# power.net
KiCad netlist of a schematic drawn in Altium Designer
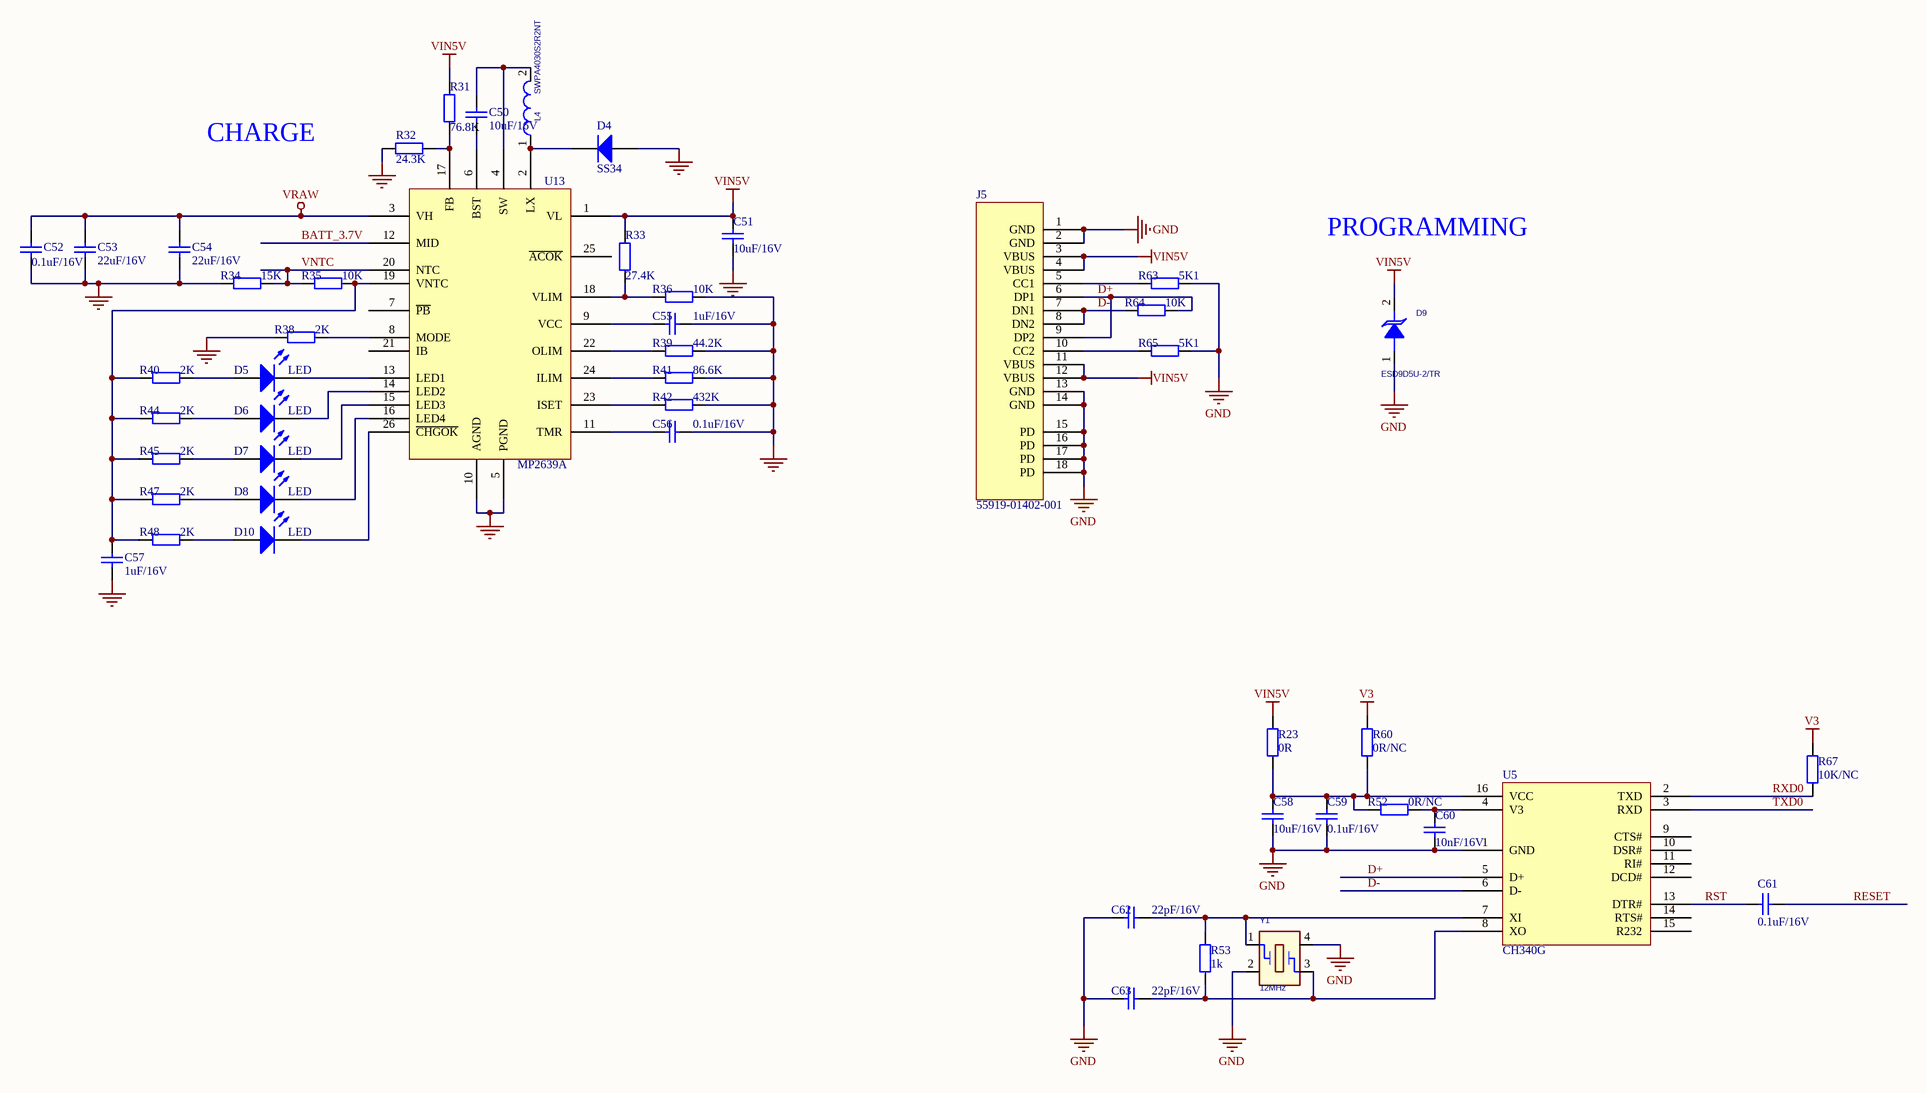
[diagram p0: power.SchDoc]

(export (version "E")
  (design (tool "Eeschema 10.0.6"))
  (components
    (comp (ref "C50")
      (value "10uF/16V")
      (footprint "CAPC1608N")
      (description "Capacitor")
      (libsource (lib "altium-import") (part "root_1_Cap_2_"))
    )
    (comp (ref "C51")
      (value "10uF/16V")
      (footprint "CAPC1608N")
      (description "Capacitor")
      (libsource (lib "altium-import") (part "root_1_Cap_2_"))
    )
    (comp (ref "C52")
      (value "0.1uF/16V")
      (footprint "CAPC1608N")
      (description "Capacitor")
      (libsource (lib "altium-import") (part "root_1_Cap_2_"))
    )
    (comp (ref "C53")
      (value "22uF/16V")
      (footprint "CAPC2012N")
      (description "Capacitor")
      (libsource (lib "altium-import") (part "root_1_Cap_2_"))
    )
    (comp (ref "C54")
      (value "22uF/16V")
      (footprint "CAPC2012N")
      (description "Capacitor")
      (libsource (lib "altium-import") (part "root_1_Cap_2_"))
    )
    (comp (ref "C55")
      (value "1uF/16V")
      (footprint "CAPC1608N")
      (description "Capacitor")
      (libsource (lib "altium-import") (part "root_2_Cap_2_"))
    )
    (comp (ref "C56")
      (value "0.1uF/16V")
      (footprint "CAPC1608N")
      (description "Capacitor")
      (libsource (lib "altium-import") (part "root_2_Cap_2_"))
    )
    (comp (ref "C57")
      (value "1uF/16V")
      (footprint "CAPC1608N")
      (description "Capacitor")
      (libsource (lib "altium-import") (part "root_1_Cap_2_"))
    )
    (comp (ref "C58")
      (value "10uF/16V")
      (footprint "CAPC1608N")
      (description "Capacitor")
      (libsource (lib "altium-import") (part "root_3_Cap_2_"))
    )
    (comp (ref "C59")
      (value "0.1uF/16V")
      (footprint "CAPC1608N")
      (description "Capacitor")
      (libsource (lib "altium-import") (part "root_3_Cap_2_"))
    )
    (comp (ref "C60")
      (value "10nF/16V")
      (footprint "CAPC1608N")
      (description "Capacitor")
      (libsource (lib "altium-import") (part "root_3_Cap_2_"))
    )
    (comp (ref "C61")
      (value "0.1uF/16V")
      (footprint "CAPC1608N")
      (description "Capacitor")
      (libsource (lib "altium-import") (part "root_0_Cap_2_"))
    )
    (comp (ref "C62")
      (value "22pF/16V")
      (footprint "CAPC1608N")
      (description "Capacitor")
      (libsource (lib "altium-import") (part "root_2_Cap_2_"))
    )
    (comp (ref "C63")
      (value "22pF/16V")
      (footprint "CAPC1608N")
      (description "Capacitor")
      (libsource (lib "altium-import") (part "root_2_Cap_2_"))
    )
    (comp (ref "D4")
      (value "SS34")
      (footprint "SMB")
      (description "Default Diode")
      (fields (field (name "PUBLISHER") "Altium Limited"))
      (libsource (lib "Component") (part "DIODE"))
    )
    (comp (ref "D5")
      (value "LED")
      (footprint "0603LED G")
      (description "Typical INFRARED GaAs LED")
      (fields (field (name "PUBLISHER") "Altium Limited"))
      (libsource (lib "Miscellaneous Devices") (part "LED0"))
    )
    (comp (ref "D6")
      (value "LED")
      (footprint "0603LED G")
      (description "Typical INFRARED GaAs LED")
      (fields (field (name "PUBLISHER") "Altium Limited"))
      (libsource (lib "Miscellaneous Devices") (part "LED0"))
    )
    (comp (ref "D7")
      (value "LED")
      (footprint "0603LED G")
      (description "Typical INFRARED GaAs LED")
      (fields (field (name "PUBLISHER") "Altium Limited"))
      (libsource (lib "Miscellaneous Devices") (part "LED0"))
    )
    (comp (ref "D8")
      (value "LED")
      (footprint "0603LED G")
      (description "Typical INFRARED GaAs LED")
      (fields (field (name "PUBLISHER") "Altium Limited"))
      (libsource (lib "Miscellaneous Devices") (part "LED0"))
    )
    (comp (ref "D9")
      (value "ESD9D5U-2/TR")
      (footprint "sod-923")
      (description "DIODE TVS ESD PROT ULT LOW CAP 5-5.4V SOD-923")
      (libsource (lib "*") (part "DIODE_TVS"))
    )
    (comp (ref "D10")
      (value "LED")
      (footprint "0603LED G")
      (description "Typical INFRARED GaAs LED")
      (fields (field (name "PUBLISHER") "Altium Limited"))
      (libsource (lib "Miscellaneous Devices") (part "LED0"))
    )
    (comp (ref "J5")
      (value "55919-01402-001")
      (footprint "55919-01402-001")
      (libsource (lib "COMMODEVICES") (part "55919-01402-001"))
    )
    (comp (ref "L4")
      (value "SWPA4030S2R2NT")
      (footprint "L4X4")
      (description "Inductor 2.2uH smt 2.6A, 58 milliohm")
      (fields (field (name "MFR") "TDK") (field (name "TIINTPARTNUMBER") "1L0025"))
      (libsource (lib "*") (part "IND_2.2uH_2.6A_10%_SMD"))
    )
    (comp (ref "R23")
      (value "0R")
      (footprint "RESC1608N")
      (description "Resistor")
      (libsource (lib "") (part "Res2_2"))
    )
    (comp (ref "R31")
      (value "76.8K")
      (footprint "RESC1608N")
      (description "Resistor")
      (libsource (lib "") (part "Res2_2"))
    )
    (comp (ref "R32")
      (value "24.3K")
      (footprint "RESC1608N")
      (description "Resistor")
      (libsource (lib "") (part "Res2_1"))
    )
    (comp (ref "R33")
      (value "27.4K")
      (footprint "RESC1608N")
      (description "Resistor")
      (libsource (lib "") (part "Res2_2"))
    )
    (comp (ref "R34")
      (value "15K")
      (footprint "RESC1608N")
      (description "Resistor")
      (libsource (lib "*") (part "Res2"))
    )
    (comp (ref "R35")
      (value "10K")
      (footprint "RESC1608N")
      (description "Resistor")
      (libsource (lib "*") (part "Res2"))
    )
    (comp (ref "R36")
      (value "10K")
      (footprint "RESC1608N")
      (description "Resistor")
      (libsource (lib "") (part "Res2_1"))
    )
    (comp (ref "R38")
      (value "2K")
      (footprint "RESC1608N")
      (description "Resistor")
      (libsource (lib "*") (part "Res2"))
    )
    (comp (ref "R39")
      (value "44.2K")
      (footprint "RESC1608N")
      (description "Resistor")
      (libsource (lib "") (part "Res2_1"))
    )
    (comp (ref "R40")
      (value "2K")
      (footprint "RESC1608N")
      (description "Resistor")
      (libsource (lib "*") (part "Res2"))
    )
    (comp (ref "R41")
      (value "86.6K")
      (footprint "RESC1608N")
      (description "Resistor")
      (libsource (lib "") (part "Res2_1"))
    )
    (comp (ref "R42")
      (value "432K")
      (footprint "RESC1608N")
      (description "Resistor")
      (libsource (lib "") (part "Res2_1"))
    )
    (comp (ref "R44")
      (value "2K")
      (footprint "RESC1608N")
      (description "Resistor")
      (libsource (lib "*") (part "Res2"))
    )
    (comp (ref "R45")
      (value "2K")
      (footprint "RESC1608N")
      (description "Resistor")
      (libsource (lib "*") (part "Res2"))
    )
    (comp (ref "R47")
      (value "2K")
      (footprint "RESC1608N")
      (description "Resistor")
      (libsource (lib "*") (part "Res2"))
    )
    (comp (ref "R48")
      (value "2K")
      (footprint "RESC1608N")
      (description "Resistor")
      (libsource (lib "*") (part "Res2"))
    )
    (comp (ref "R52")
      (value "0R/NC")
      (footprint "RESC1608N")
      (description "Resistor")
      (libsource (lib "*") (part "Res2"))
    )
    (comp (ref "R53")
      (value "1k")
      (footprint "RESC1608N")
      (description "Resistor")
      (fields (field (name "PUBLISHER") "Altium Limited"))
      (libsource (lib "*") (part "Res2"))
    )
    (comp (ref "R60")
      (value "0R/NC")
      (footprint "RESC1608N")
      (description "Resistor")
      (libsource (lib "") (part "Res2_2"))
    )
    (comp (ref "R63")
      (value "5K1")
      (footprint "RESC1608N")
      (description "Resistor")
      (libsource (lib "*") (part "Res2"))
    )
    (comp (ref "R64")
      (value "10K")
      (footprint "RESC1608N")
      (description "Resistor")
      (libsource (lib "") (part "Res2_1"))
    )
    (comp (ref "R65")
      (value "5K1")
      (footprint "RESC1608N")
      (description "Resistor")
      (libsource (lib "*") (part "Res2"))
    )
    (comp (ref "R67")
      (value "10K/NC")
      (footprint "RESC1608N")
      (description "Resistor")
      (libsource (lib "") (part "Res2_2"))
    )
    (comp (ref "U5") (value "CH340G") (footprint "sop16") (libsource (lib "COMMODEVICES") (part "CH340G")))
    (comp (ref "U13") (value "MP2639A") (footprint "MP2639A") (libsource (lib "plobot") (part "MP2639A")))
    (comp (ref "Y1") (value "12MHz") (footprint "XTAL-3225") (libsource (lib "*") (part "XTAL_13Y_A")))
  )
  (nets
    (net (code "1") (name "/BATT_3.7V") (class "Default")
      (node (ref "U13") (pin "12") (pinfunction "MID_12") (pintype "power_in"))
    )
    (net (code "2") (name "/D+") (class "Default")
      (node (ref "J5") (pin "6") (pinfunction "DP1_6") (pintype "passive"))
      (node (ref "J5") (pin "9") (pinfunction "DP2_9") (pintype "passive"))
      (node (ref "R64") (pin "2") (pinfunction "2_2") (pintype "passive"))
      (node (ref "U5") (pin "5") (pinfunction "D+_5") (pintype "passive"))
    )
    (net (code "3") (name "/D-") (class "Default")
      (node (ref "J5") (pin "7") (pinfunction "DN1_7") (pintype "passive"))
      (node (ref "J5") (pin "8") (pinfunction "DN2_8") (pintype "passive"))
      (node (ref "R64") (pin "1") (pinfunction "1_1") (pintype "passive"))
      (node (ref "U5") (pin "6") (pinfunction "D-_6") (pintype "passive"))
    )
    (net (code "4") (name "/RESET") (class "Default")
      (node (ref "C61") (pin "2") (pinfunction "2_2") (pintype "passive"))
    )
    (net (code "5") (name "/RST") (class "Default")
      (node (ref "C61") (pin "1") (pinfunction "1_1") (pintype "passive"))
      (node (ref "U5") (pin "13") (pinfunction "DTR#_13") (pintype "passive"))
    )
    (net (code "6") (name "/RXD0") (class "Default")
      (node (ref "R67") (pin "2") (pinfunction "2_2") (pintype "passive"))
      (node (ref "U5") (pin "2") (pinfunction "TXD_2") (pintype "passive"))
    )
    (net (code "7") (name "/TXD0") (class "Default")
      (node (ref "U5") (pin "3") (pinfunction "RXD_3") (pintype "passive"))
    )
    (net (code "8") (name "/VNTC") (class "Default")
      (node (ref "R34") (pin "1") (pinfunction "1_1") (pintype "passive"))
      (node (ref "R35") (pin "2") (pinfunction "2_2") (pintype "passive"))
      (node (ref "U13") (pin "20") (pinfunction "NTC_20") (pintype "power_in"))
    )
    (net (code "9") (name "GND") (class "Default")
      (node (ref "C51") (pin "1") (pinfunction "1_1") (pintype "passive"))
      (node (ref "C52") (pin "1") (pinfunction "1_1") (pintype "passive"))
      (node (ref "C53") (pin "1") (pinfunction "1_1") (pintype "passive"))
      (node (ref "C54") (pin "1") (pinfunction "1_1") (pintype "passive"))
      (node (ref "C55") (pin "1") (pinfunction "1_1") (pintype "passive"))
      (node (ref "C56") (pin "1") (pinfunction "1_1") (pintype "passive"))
      (node (ref "C57") (pin "1") (pinfunction "1_1") (pintype "passive"))
      (node (ref "C58") (pin "2") (pinfunction "2_2") (pintype "passive"))
      (node (ref "C59") (pin "2") (pinfunction "2_2") (pintype "passive"))
      (node (ref "C60") (pin "2") (pinfunction "2_2") (pintype "passive"))
      (node (ref "C62") (pin "2") (pinfunction "2_2") (pintype "passive"))
      (node (ref "C63") (pin "2") (pinfunction "2_2") (pintype "passive"))
      (node (ref "D4") (pin "1") (pinfunction "A_1") (pintype "passive"))
      (node (ref "D9") (pin "1") (pinfunction "1_1") (pintype "passive"))
      (node (ref "J5") (pin "1") (pinfunction "GND_1") (pintype "passive"))
      (node (ref "J5") (pin "13") (pinfunction "GND_13") (pintype "passive"))
      (node (ref "J5") (pin "14") (pinfunction "GND_14") (pintype "passive"))
      (node (ref "J5") (pin "15") (pinfunction "PD_15") (pintype "passive"))
      (node (ref "J5") (pin "16") (pinfunction "PD_16") (pintype "passive"))
      (node (ref "J5") (pin "17") (pinfunction "PD_17") (pintype "passive"))
      (node (ref "J5") (pin "18") (pinfunction "PD_18") (pintype "passive"))
      (node (ref "J5") (pin "2") (pinfunction "GND_2") (pintype "passive"))
      (node (ref "R32") (pin "1") (pinfunction "1_1") (pintype "passive"))
      (node (ref "R34") (pin "2") (pinfunction "2_2") (pintype "passive"))
      (node (ref "R36") (pin "2") (pinfunction "2_2") (pintype "passive"))
      (node (ref "R38") (pin "2") (pinfunction "2_2") (pintype "passive"))
      (node (ref "R39") (pin "2") (pinfunction "2_2") (pintype "passive"))
      (node (ref "R41") (pin "2") (pinfunction "2_2") (pintype "passive"))
      (node (ref "R42") (pin "2") (pinfunction "2_2") (pintype "passive"))
      (node (ref "R63") (pin "1") (pinfunction "1_1") (pintype "passive"))
      (node (ref "R65") (pin "1") (pinfunction "1_1") (pintype "passive"))
      (node (ref "U13") (pin "10") (pinfunction "AGND_10") (pintype "power_in"))
      (node (ref "U13") (pin "5") (pinfunction "PGND_5") (pintype "power_in"))
      (node (ref "U5") (pin "1") (pinfunction "GND_1") (pintype "passive"))
      (node (ref "Y1") (pin "2") (pinfunction "2_2") (pintype "passive"))
      (node (ref "Y1") (pin "4") (pinfunction "4_4") (pintype "passive"))
    )
    (net (code "10") (name "Net-(D4-K)") (class "Default")
      (node (ref "D4") (pin "2") (pinfunction "K_2") (pintype "passive"))
      (node (ref "L4") (pin "1") (pinfunction "1_1") (pintype "passive"))
      (node (ref "U13") (pin "2") (pinfunction "LX_2") (pintype "power_in"))
    )
    (net (code "11") (name "Net-(D5-A)") (class "Default")
      (node (ref "D5") (pin "1") (pinfunction "A_1") (pintype "passive"))
      (node (ref "R40") (pin "1") (pinfunction "1_1") (pintype "passive"))
    )
    (net (code "12") (name "Net-(D5-K)") (class "Default")
      (node (ref "D5") (pin "2") (pinfunction "K_2") (pintype "passive"))
      (node (ref "U13") (pin "13") (pinfunction "LED1_13") (pintype "power_in"))
    )
    (net (code "13") (name "Net-(D6-A)") (class "Default")
      (node (ref "D6") (pin "1") (pinfunction "A_1") (pintype "passive"))
      (node (ref "R44") (pin "1") (pinfunction "1_1") (pintype "passive"))
    )
    (net (code "14") (name "Net-(D6-K)") (class "Default")
      (node (ref "D6") (pin "2") (pinfunction "K_2") (pintype "passive"))
      (node (ref "U13") (pin "14") (pinfunction "LED2_14") (pintype "power_in"))
    )
    (net (code "15") (name "Net-(D7-A)") (class "Default")
      (node (ref "D7") (pin "1") (pinfunction "A_1") (pintype "passive"))
      (node (ref "R45") (pin "1") (pinfunction "1_1") (pintype "passive"))
    )
    (net (code "16") (name "Net-(D7-K)") (class "Default")
      (node (ref "D7") (pin "2") (pinfunction "K_2") (pintype "passive"))
      (node (ref "U13") (pin "15") (pinfunction "LED3_15") (pintype "power_in"))
    )
    (net (code "17") (name "Net-(D8-A)") (class "Default")
      (node (ref "D8") (pin "1") (pinfunction "A_1") (pintype "passive"))
      (node (ref "R47") (pin "1") (pinfunction "1_1") (pintype "passive"))
    )
    (net (code "18") (name "Net-(D8-K)") (class "Default")
      (node (ref "D8") (pin "2") (pinfunction "K_2") (pintype "passive"))
      (node (ref "U13") (pin "16") (pinfunction "LED4_16") (pintype "power_in"))
    )
    (net (code "19") (name "Net-(D10-A)") (class "Default")
      (node (ref "D10") (pin "1") (pinfunction "A_1") (pintype "passive"))
      (node (ref "R48") (pin "1") (pinfunction "1_1") (pintype "passive"))
    )
    (net (code "20") (name "Net-(D10-K)") (class "Default")
      (node (ref "D10") (pin "2") (pinfunction "K_2") (pintype "passive"))
      (node (ref "U13") (pin "26") (pinfunction "~{CHGOK}_26") (pintype "power_in"))
    )
    (net (code "21") (name "Net-(J5-CC1)") (class "Default")
      (node (ref "J5") (pin "5") (pinfunction "CC1_5") (pintype "passive"))
      (node (ref "R63") (pin "2") (pinfunction "2_2") (pintype "passive"))
    )
    (net (code "22") (name "Net-(J5-CC2)") (class "Default")
      (node (ref "J5") (pin "10") (pinfunction "CC2_10") (pintype "passive"))
      (node (ref "R65") (pin "2") (pinfunction "2_2") (pintype "passive"))
    )
    (net (code "23") (name "Net-(U5-V3)") (class "Default")
      (node (ref "C60") (pin "1") (pinfunction "1_1") (pintype "passive"))
      (node (ref "R52") (pin "1") (pinfunction "1_1") (pintype "passive"))
      (node (ref "U5") (pin "4") (pinfunction "V3_4") (pintype "passive"))
    )
    (net (code "24") (name "Net-(U5-VCC)") (class "Default")
      (node (ref "C58") (pin "1") (pinfunction "1_1") (pintype "passive"))
      (node (ref "C59") (pin "1") (pinfunction "1_1") (pintype "passive"))
      (node (ref "R23") (pin "2") (pinfunction "2_2") (pintype "passive"))
      (node (ref "R52") (pin "2") (pinfunction "2_2") (pintype "passive"))
      (node (ref "R60") (pin "2") (pinfunction "2_2") (pintype "passive"))
      (node (ref "U5") (pin "16") (pinfunction "VCC_16") (pintype "passive"))
    )
    (net (code "25") (name "Net-(U5-XI)") (class "Default")
      (node (ref "C62") (pin "1") (pinfunction "1_1") (pintype "passive"))
      (node (ref "R53") (pin "1") (pinfunction "1_1") (pintype "passive"))
      (node (ref "U5") (pin "7") (pinfunction "XI_7") (pintype "passive"))
      (node (ref "Y1") (pin "1") (pinfunction "1_1") (pintype "passive"))
    )
    (net (code "26") (name "Net-(U5-XO)") (class "Default")
      (node (ref "C63") (pin "1") (pinfunction "1_1") (pintype "passive"))
      (node (ref "R53") (pin "2") (pinfunction "2_2") (pintype "passive"))
      (node (ref "U5") (pin "8") (pinfunction "XO_8") (pintype "passive"))
      (node (ref "Y1") (pin "3") (pinfunction "3_3") (pintype "passive"))
    )
    (net (code "27") (name "Net-(U13-BST)") (class "Default")
      (node (ref "C50") (pin "1") (pinfunction "1_1") (pintype "passive"))
      (node (ref "U13") (pin "6") (pinfunction "BST_6") (pintype "power_in"))
    )
    (net (code "28") (name "Net-(U13-FB)") (class "Default")
      (node (ref "R31") (pin "2") (pinfunction "2_2") (pintype "passive"))
      (node (ref "R32") (pin "2") (pinfunction "2_2") (pintype "passive"))
      (node (ref "U13") (pin "17") (pinfunction "FB_17") (pintype "power_in"))
    )
    (net (code "29") (name "Net-(U13-ILIM)") (class "Default")
      (node (ref "R41") (pin "1") (pinfunction "1_1") (pintype "passive"))
      (node (ref "U13") (pin "24") (pinfunction "ILIM_24") (pintype "power_in"))
    )
    (net (code "30") (name "Net-(U13-ISET)") (class "Default")
      (node (ref "R42") (pin "1") (pinfunction "1_1") (pintype "passive"))
      (node (ref "U13") (pin "23") (pinfunction "ISET_23") (pintype "power_in"))
    )
    (net (code "31") (name "Net-(U13-MODE)") (class "Default")
      (node (ref "R38") (pin "1") (pinfunction "1_1") (pintype "passive"))
      (node (ref "U13") (pin "8") (pinfunction "MODE_8") (pintype "power_in"))
    )
    (net (code "32") (name "Net-(U13-OLIM)") (class "Default")
      (node (ref "R39") (pin "1") (pinfunction "1_1") (pintype "passive"))
      (node (ref "U13") (pin "22") (pinfunction "OLIM_22") (pintype "power_in"))
    )
    (net (code "33") (name "Net-(U13-SW)") (class "Default")
      (node (ref "C50") (pin "2") (pinfunction "2_2") (pintype "passive"))
      (node (ref "L4") (pin "2") (pinfunction "2_2") (pintype "passive"))
      (node (ref "U13") (pin "4") (pinfunction "SW_4") (pintype "power_in"))
    )
    (net (code "34") (name "Net-(U13-TMR)") (class "Default")
      (node (ref "C56") (pin "2") (pinfunction "2_2") (pintype "passive"))
      (node (ref "U13") (pin "11") (pinfunction "TMR_11") (pintype "power_in"))
    )
    (net (code "35") (name "Net-(U13-VCC)") (class "Default")
      (node (ref "C55") (pin "2") (pinfunction "2_2") (pintype "passive"))
      (node (ref "U13") (pin "9") (pinfunction "VCC_9") (pintype "power_in"))
    )
    (net (code "36") (name "Net-(U13-VLIM)") (class "Default")
      (node (ref "R33") (pin "2") (pinfunction "2_2") (pintype "passive"))
      (node (ref "R36") (pin "1") (pinfunction "1_1") (pintype "passive"))
      (node (ref "U13") (pin "18") (pinfunction "VLIM_18") (pintype "power_in"))
    )
    (net (code "37") (name "Net-(U13-VNTC)") (class "Default")
      (node (ref "C57") (pin "2") (pinfunction "2_2") (pintype "passive"))
      (node (ref "R35") (pin "1") (pinfunction "1_1") (pintype "passive"))
      (node (ref "R40") (pin "2") (pinfunction "2_2") (pintype "passive"))
      (node (ref "R44") (pin "2") (pinfunction "2_2") (pintype "passive"))
      (node (ref "R45") (pin "2") (pinfunction "2_2") (pintype "passive"))
      (node (ref "R47") (pin "2") (pinfunction "2_2") (pintype "passive"))
      (node (ref "R48") (pin "2") (pinfunction "2_2") (pintype "passive"))
      (node (ref "U13") (pin "19") (pinfunction "VNTC_19") (pintype "power_in"))
    )
    (net (code "38") (name "V3") (class "Default")
      (node (ref "R60") (pin "1") (pinfunction "1_1") (pintype "passive"))
      (node (ref "R67") (pin "1") (pinfunction "1_1") (pintype "passive"))
    )
    (net (code "39") (name "VIN5V") (class "Default")
      (node (ref "C51") (pin "2") (pinfunction "2_2") (pintype "passive"))
      (node (ref "D9") (pin "2") (pinfunction "2_2") (pintype "passive"))
      (node (ref "J5") (pin "11") (pinfunction "VBUS_11") (pintype "passive"))
      (node (ref "J5") (pin "12") (pinfunction "VBUS_12") (pintype "passive"))
      (node (ref "J5") (pin "3") (pinfunction "VBUS_3") (pintype "passive"))
      (node (ref "J5") (pin "4") (pinfunction "VBUS_4") (pintype "passive"))
      (node (ref "R23") (pin "1") (pinfunction "1_1") (pintype "passive"))
      (node (ref "R31") (pin "1") (pinfunction "1_1") (pintype "passive"))
      (node (ref "R33") (pin "1") (pinfunction "1_1") (pintype "passive"))
      (node (ref "U13") (pin "1") (pinfunction "VL_1") (pintype "power_in"))
    )
    (net (code "40") (name "VRAW") (class "Default")
      (node (ref "C52") (pin "2") (pinfunction "2_2") (pintype "passive"))
      (node (ref "C53") (pin "2") (pinfunction "2_2") (pintype "passive"))
      (node (ref "C54") (pin "2") (pinfunction "2_2") (pintype "passive"))
      (node (ref "U13") (pin "3") (pinfunction "VH_3") (pintype "power_in"))
    )
    (net (code "41") (name "unconnected-(U5-CTS#-Pad9)") (class "Default")
      (node (ref "U5") (pin "9") (pinfunction "CTS#_9") (pintype "passive"))
    )
    (net (code "42") (name "unconnected-(U5-DCD#-Pad12)") (class "Default")
      (node (ref "U5") (pin "12") (pinfunction "DCD#_12") (pintype "passive"))
    )
    (net (code "43") (name "unconnected-(U5-DSR#-Pad10)") (class "Default")
      (node (ref "U5") (pin "10") (pinfunction "DSR#_10") (pintype "passive"))
    )
    (net (code "44") (name "unconnected-(U5-R232-Pad15)") (class "Default")
      (node (ref "U5") (pin "15") (pinfunction "R232_15") (pintype "passive"))
    )
    (net (code "45") (name "unconnected-(U5-RI#-Pad11)") (class "Default")
      (node (ref "U5") (pin "11") (pinfunction "RI#_11") (pintype "passive"))
    )
    (net (code "46") (name "unconnected-(U5-RTS#-Pad14)") (class "Default")
      (node (ref "U5") (pin "14") (pinfunction "RTS#_14") (pintype "passive"))
    )
    (net (code "47") (name "unconnected-(U13-IB-Pad21)") (class "Default")
      (node (ref "U13") (pin "21") (pinfunction "IB_21") (pintype "power_in"))
    )
    (net (code "48") (name "unconnected-(U13-~{ACOK}-Pad25)") (class "Default")
      (node (ref "U13") (pin "25") (pinfunction "~{ACOK}_25") (pintype "power_in"))
    )
    (net (code "49") (name "unconnected-(U13-~{PB}-Pad7)") (class "Default")
      (node (ref "U13") (pin "7") (pinfunction "~{PB}_7") (pintype "power_in"))
    )
  )
)
